# controller.net
KiCad netlist of a schematic drawn in Altium Designer
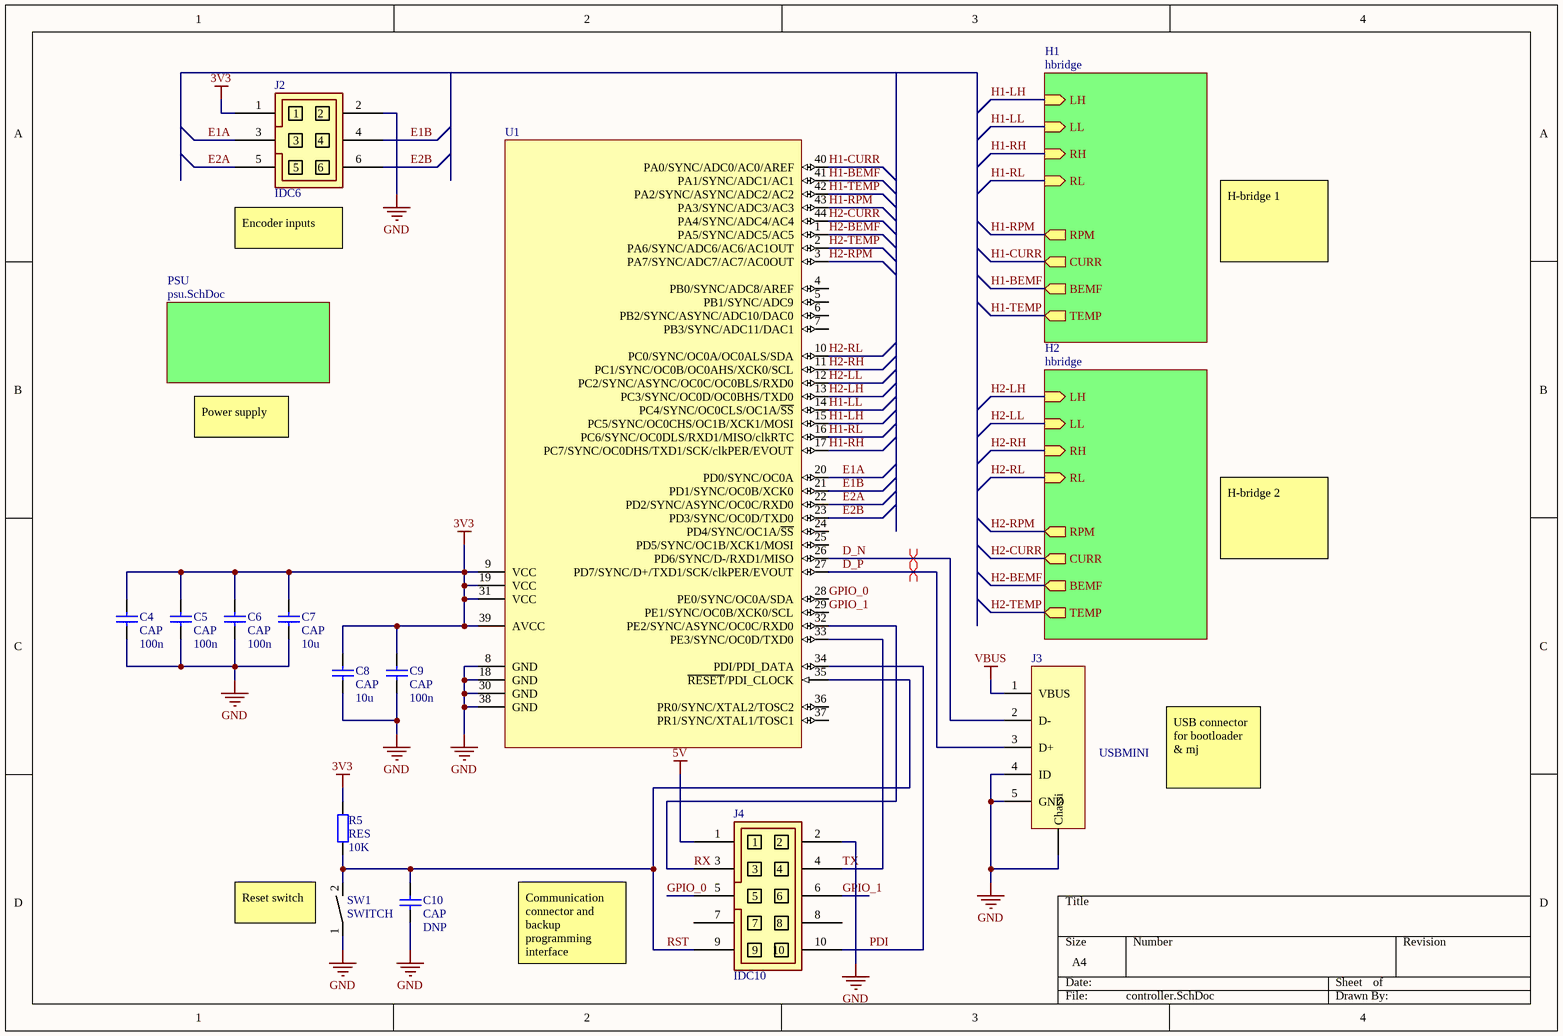
[diagram p0: controller.SchDoc]

(export (version "E")
  (design (tool "Eeschema 10.0.6"))
  (components
    (comp (ref "C4")
      (value "CAP")
      (footprint "CAPC1608X08M")
      (description "Capacitor")
      (fields (field (name "ALTIUM_VALUE") "100n") (field (name "PUBLISHER") "Altium Limited"))
      (libsource (lib "std") (part "CAP"))
    )
    (comp (ref "C5")
      (value "CAP")
      (footprint "CAPC1608X08M")
      (description "Capacitor")
      (fields (field (name "ALTIUM_VALUE") "100n") (field (name "PUBLISHER") "Altium Limited"))
      (libsource (lib "std") (part "CAP"))
    )
    (comp (ref "C6")
      (value "CAP")
      (footprint "CAPC1608X08M")
      (description "Capacitor")
      (fields (field (name "ALTIUM_VALUE") "100n") (field (name "PUBLISHER") "Altium Limited"))
      (libsource (lib "std") (part "CAP"))
    )
    (comp (ref "C7")
      (value "CAP")
      (footprint "CAPC1608X08M")
      (description "Capacitor")
      (fields (field (name "ALTIUM_VALUE") "10u") (field (name "PUBLISHER") "Altium Limited"))
      (libsource (lib "std") (part "CAP"))
    )
    (comp (ref "C8")
      (value "CAP")
      (footprint "CAPC2012X11M")
      (description "Capacitor")
      (fields (field (name "ALTIUM_VALUE") "10u") (field (name "PUBLISHER") "Altium Limited"))
      (libsource (lib "std") (part "CAP"))
    )
    (comp (ref "C9")
      (value "CAP")
      (footprint "CAPC1608X08M")
      (description "Capacitor")
      (fields (field (name "ALTIUM_VALUE") "100n") (field (name "PUBLISHER") "Altium Limited"))
      (libsource (lib "std") (part "CAP"))
    )
    (comp (ref "C10")
      (value "CAP")
      (footprint "CAPC1608X08M")
      (description "Capacitor")
      (fields (field (name "ALTIUM_VALUE") "DNP") (field (name "PUBLISHER") "Altium Limited"))
      (libsource (lib "std") (part "CAP"))
    )
    (comp (ref "J2")
      (value "IDC6")
      (footprint "IDC6")
      (description "6pin IDC connector")
      (libsource (lib "std") (part "IDC6"))
    )
    (comp (ref "J3") (value "USBMINI") (footprint "MINI_USB") (libsource (lib "std") (part "MINI_USB")))
    (comp (ref "J4")
      (value "IDC10")
      (footprint "IDC10")
      (description "10pin IDC connector")
      (libsource (lib "std") (part "IDC10"))
    )
    (comp (ref "R5")
      (value "RES")
      (footprint "RESC1608X06M")
      (description "Resistor")
      (fields (field (name "ALTIUM_VALUE") "10K") (field (name "PUBLISHER") "Altium Limited"))
      (libsource (lib "std") (part "RES"))
    )
    (comp (ref "SW1")
      (value "SWITCH")
      (footprint "Switch_pad")
      (description "Switch")
      (libsource (lib "std") (part "Switch"))
    )
    (comp (ref "U1")
      (value "~")
      (footprint "44A_N")
      (libsource (lib "Atmel Microcontroller AVR XMEGA") (part "ATxmega32A4U-AU"))
    )
  )
  (nets
    (net (code "1") (name "/D_N") (class "Default")
      (node (ref "J3") (pin "2") (pinfunction "D-_2") (pintype "passive"))
      (node (ref "U1") (pin "26") (pinfunction "PD6/SYNC/D-/RXD1/MISO_26") (pintype "bidirectional"))
    )
    (net (code "2") (name "/D_P") (class "Default")
      (node (ref "J3") (pin "3") (pinfunction "D+_3") (pintype "passive"))
      (node (ref "U1") (pin "27") (pinfunction "PD7/SYNC/D+/TXD1/SCK/clkPER/EVOUT_27") (pintype "bidirectional"))
    )
    (net (code "3") (name "/E1A") (class "Default")
      (node (ref "J2") (pin "3") (pinfunction "3_3") (pintype "passive"))
      (node (ref "U1") (pin "20") (pinfunction "PD0/SYNC/OC0A_20") (pintype "bidirectional"))
    )
    (net (code "4") (name "/E1B") (class "Default")
      (node (ref "J2") (pin "4") (pinfunction "4_4") (pintype "passive"))
      (node (ref "U1") (pin "21") (pinfunction "PD1/SYNC/OC0B/XCK0_21") (pintype "bidirectional"))
    )
    (net (code "5") (name "/E2A") (class "Default")
      (node (ref "J2") (pin "5") (pinfunction "5_5") (pintype "passive"))
      (node (ref "U1") (pin "22") (pinfunction "PD2/SYNC/ASYNC/OC0C/RXD0_22") (pintype "bidirectional"))
    )
    (net (code "6") (name "/E2B") (class "Default")
      (node (ref "J2") (pin "6") (pinfunction "6_6") (pintype "passive"))
      (node (ref "U1") (pin "23") (pinfunction "PD3/SYNC/OC0D/TXD0_23") (pintype "bidirectional"))
    )
    (net (code "7") (name "/GPIO_0") (class "Default")
      (node (ref "J4") (pin "5") (pinfunction "5_5") (pintype "passive"))
      (node (ref "U1") (pin "28") (pinfunction "PE0/SYNC/OC0A/SDA_28") (pintype "bidirectional"))
    )
    (net (code "8") (name "/GPIO_1") (class "Default")
      (node (ref "J4") (pin "6") (pinfunction "6_6") (pintype "passive"))
      (node (ref "U1") (pin "29") (pinfunction "PE1/SYNC/OC0B/XCK0/SCL_29") (pintype "bidirectional"))
    )
    (net (code "9") (name "/H1-BEMF") (class "Default")
      (node (ref "U1") (pin "41") (pinfunction "PA1/SYNC/ADC1/AC1_41") (pintype "bidirectional"))
    )
    (net (code "10") (name "/H1-CURR") (class "Default")
      (node (ref "U1") (pin "40") (pinfunction "PA0/SYNC/ADC0/AC0/AREF_40") (pintype "bidirectional"))
    )
    (net (code "11") (name "/H1-LH") (class "Default")
      (node (ref "U1") (pin "15") (pinfunction "PC5/SYNC/OC0CHS/OC1B/XCK1/MOSI_15") (pintype "bidirectional"))
    )
    (net (code "12") (name "/H1-LL") (class "Default")
      (node (ref "U1") (pin "14") (pinfunction "PC4/SYNC/OC0CLS/OC1A/~{SS}_14") (pintype "bidirectional"))
    )
    (net (code "13") (name "/H1-RH") (class "Default")
      (node (ref "U1") (pin "17") (pinfunction "PC7/SYNC/OC0DHS/TXD1/SCK/clkPER/EVOUT_17") (pintype "bidirectional"))
    )
    (net (code "14") (name "/H1-RL") (class "Default")
      (node (ref "U1") (pin "16") (pinfunction "PC6/SYNC/OC0DLS/RXD1/MISO/clkRTC_16") (pintype "bidirectional"))
    )
    (net (code "15") (name "/H1-RPM") (class "Default")
      (node (ref "U1") (pin "43") (pinfunction "PA3/SYNC/ADC3/AC3_43") (pintype "bidirectional"))
    )
    (net (code "16") (name "/H1-TEMP") (class "Default")
      (node (ref "U1") (pin "42") (pinfunction "PA2/SYNC/ASYNC/ADC2/AC2_42") (pintype "bidirectional"))
    )
    (net (code "17") (name "/H2-BEMF") (class "Default")
      (node (ref "U1") (pin "1") (pinfunction "PA5/SYNC/ADC5/AC5_1") (pintype "bidirectional"))
    )
    (net (code "18") (name "/H2-CURR") (class "Default")
      (node (ref "U1") (pin "44") (pinfunction "PA4/SYNC/ADC4/AC4_44") (pintype "bidirectional"))
    )
    (net (code "19") (name "/H2-LH") (class "Default")
      (node (ref "U1") (pin "13") (pinfunction "PC3/SYNC/OC0D/OC0BHS/TXD0_13") (pintype "bidirectional"))
    )
    (net (code "20") (name "/H2-LL") (class "Default")
      (node (ref "U1") (pin "12") (pinfunction "PC2/SYNC/ASYNC/OC0C/OC0BLS/RXD0_12") (pintype "bidirectional"))
    )
    (net (code "21") (name "/H2-RH") (class "Default")
      (node (ref "U1") (pin "11") (pinfunction "PC1/SYNC/OC0B/OC0AHS/XCK0/SCL_11") (pintype "bidirectional"))
    )
    (net (code "22") (name "/H2-RL") (class "Default")
      (node (ref "U1") (pin "10") (pinfunction "PC0/SYNC/OC0A/OC0ALS/SDA_10") (pintype "bidirectional"))
    )
    (net (code "23") (name "/H2-RPM") (class "Default")
      (node (ref "U1") (pin "3") (pinfunction "PA7/SYNC/ADC7/AC7/AC0OUT_3") (pintype "bidirectional"))
    )
    (net (code "24") (name "/H2-TEMP") (class "Default")
      (node (ref "U1") (pin "2") (pinfunction "PA6/SYNC/ADC6/AC6/AC1OUT_2") (pintype "bidirectional"))
    )
    (net (code "25") (name "/PDI") (class "Default")
      (node (ref "J4") (pin "10") (pinfunction "10_10") (pintype "passive"))
      (node (ref "U1") (pin "34") (pinfunction "PDI/PDI_DATA_34") (pintype "bidirectional"))
    )
    (net (code "26") (name "/RST") (class "Default")
      (node (ref "C10") (pin "2") (pinfunction "2_2") (pintype "passive"))
      (node (ref "J4") (pin "9") (pinfunction "9_9") (pintype "passive"))
      (node (ref "R5") (pin "1") (pinfunction "1_1") (pintype "passive"))
      (node (ref "SW1") (pin "2") (pinfunction "2_2") (pintype "passive"))
      (node (ref "U1") (pin "35") (pinfunction "~{RESET}/PDI_CLOCK_35") (pintype "input"))
    )
    (net (code "27") (name "/RX") (class "Default")
      (node (ref "J4") (pin "3") (pinfunction "3_3") (pintype "passive"))
      (node (ref "U1") (pin "32") (pinfunction "PE2/SYNC/ASYNC/OC0C/RXD0_32") (pintype "bidirectional"))
    )
    (net (code "28") (name "/TX") (class "Default")
      (node (ref "J4") (pin "4") (pinfunction "4_4") (pintype "passive"))
      (node (ref "U1") (pin "33") (pinfunction "PE3/SYNC/OC0D/TXD0_33") (pintype "bidirectional"))
    )
    (net (code "29") (name "3V3") (class "Default")
      (node (ref "C4") (pin "2") (pinfunction "2_2") (pintype "passive"))
      (node (ref "C5") (pin "2") (pinfunction "2_2") (pintype "passive"))
      (node (ref "C6") (pin "2") (pinfunction "2_2") (pintype "passive"))
      (node (ref "C7") (pin "2") (pinfunction "2_2") (pintype "passive"))
      (node (ref "C8") (pin "2") (pinfunction "2_2") (pintype "passive"))
      (node (ref "C9") (pin "2") (pinfunction "2_2") (pintype "passive"))
      (node (ref "J2") (pin "1") (pinfunction "1_1") (pintype "passive"))
      (node (ref "R5") (pin "2") (pinfunction "2_2") (pintype "passive"))
      (node (ref "U1") (pin "19") (pinfunction "VCC_19") (pintype "power_in"))
      (node (ref "U1") (pin "31") (pinfunction "VCC_31") (pintype "power_in"))
      (node (ref "U1") (pin "39") (pinfunction "AVCC_39") (pintype "power_in"))
      (node (ref "U1") (pin "9") (pinfunction "VCC_9") (pintype "power_in"))
    )
    (net (code "30") (name "5V") (class "Default")
      (node (ref "J4") (pin "1") (pinfunction "1_1") (pintype "passive"))
    )
    (net (code "31") (name "GND") (class "Default")
      (node (ref "C10") (pin "1") (pinfunction "1_1") (pintype "passive"))
      (node (ref "C4") (pin "1") (pinfunction "1_1") (pintype "passive"))
      (node (ref "C5") (pin "1") (pinfunction "1_1") (pintype "passive"))
      (node (ref "C6") (pin "1") (pinfunction "1_1") (pintype "passive"))
      (node (ref "C7") (pin "1") (pinfunction "1_1") (pintype "passive"))
      (node (ref "C8") (pin "1") (pinfunction "1_1") (pintype "passive"))
      (node (ref "C9") (pin "1") (pinfunction "1_1") (pintype "passive"))
      (node (ref "J2") (pin "2") (pinfunction "2_2") (pintype "passive"))
      (node (ref "J3") (pin "4") (pinfunction "ID_4") (pintype "passive"))
      (node (ref "J3") (pin "5") (pinfunction "GND_5") (pintype "passive"))
      (node (ref "J3") (pin "C") (pinfunction "Chassi_C") (pintype "passive"))
      (node (ref "J4") (pin "2") (pinfunction "2_2") (pintype "passive"))
      (node (ref "SW1") (pin "1") (pinfunction "1_1") (pintype "passive"))
      (node (ref "U1") (pin "18") (pinfunction "GND_18") (pintype "power_in"))
      (node (ref "U1") (pin "30") (pinfunction "GND_30") (pintype "power_in"))
      (node (ref "U1") (pin "38") (pinfunction "GND_38") (pintype "power_in"))
      (node (ref "U1") (pin "8") (pinfunction "GND_8") (pintype "power_in"))
    )
    (net (code "32") (name "VBUS") (class "Default")
      (node (ref "J3") (pin "1") (pinfunction "VBUS_1") (pintype "passive"))
    )
    (net (code "33") (name "unconnected-(J4-Pad7)") (class "Default")
      (node (ref "J4") (pin "7") (pinfunction "7_7") (pintype "passive"))
    )
    (net (code "34") (name "unconnected-(J4-Pad8)") (class "Default")
      (node (ref "J4") (pin "8") (pinfunction "8_8") (pintype "passive"))
    )
    (net (code "35") (name "unconnected-(U1-PB0{slash}SYNC{slash}ADC8{slash}AREF-Pad4)") (class "Default")
      (node (ref "U1") (pin "4") (pinfunction "PB0/SYNC/ADC8/AREF_4") (pintype "bidirectional"))
    )
    (net (code "36") (name "unconnected-(U1-PB1{slash}SYNC{slash}ADC9-Pad5)") (class "Default")
      (node (ref "U1") (pin "5") (pinfunction "PB1/SYNC/ADC9_5") (pintype "bidirectional"))
    )
    (net (code "37") (name "unconnected-(U1-PB2{slash}SYNC{slash}ASYNC{slash}ADC10{slash}DAC0-Pad6)") (class "Default")
      (node (ref "U1") (pin "6") (pinfunction "PB2/SYNC/ASYNC/ADC10/DAC0_6") (pintype "bidirectional"))
    )
    (net (code "38") (name "unconnected-(U1-PB3{slash}SYNC{slash}ADC11{slash}DAC1-Pad7)") (class "Default")
      (node (ref "U1") (pin "7") (pinfunction "PB3/SYNC/ADC11/DAC1_7") (pintype "bidirectional"))
    )
    (net (code "39") (name "unconnected-(U1-PD4{slash}SYNC{slash}OC1A{slash}~{SS}-Pad24)") (class "Default")
      (node (ref "U1") (pin "24") (pinfunction "PD4/SYNC/OC1A/~{SS}_24") (pintype "bidirectional"))
    )
    (net (code "40") (name "unconnected-(U1-PD5{slash}SYNC{slash}OC1B{slash}XCK1{slash}MOSI-Pad25)") (class "Default")
      (node (ref "U1") (pin "25") (pinfunction "PD5/SYNC/OC1B/XCK1/MOSI_25") (pintype "bidirectional"))
    )
    (net (code "41") (name "unconnected-(U1-PR0{slash}SYNC{slash}XTAL2{slash}TOSC2-Pad36)") (class "Default")
      (node (ref "U1") (pin "36") (pinfunction "PR0/SYNC/XTAL2/TOSC2_36") (pintype "bidirectional"))
    )
    (net (code "42") (name "unconnected-(U1-PR1{slash}SYNC{slash}XTAL1{slash}TOSC1-Pad37)") (class "Default")
      (node (ref "U1") (pin "37") (pinfunction "PR1/SYNC/XTAL1/TOSC1_37") (pintype "bidirectional"))
    )
  )
)
